# transformerboard.net
KiCad netlist of a schematic drawn in EAGLE
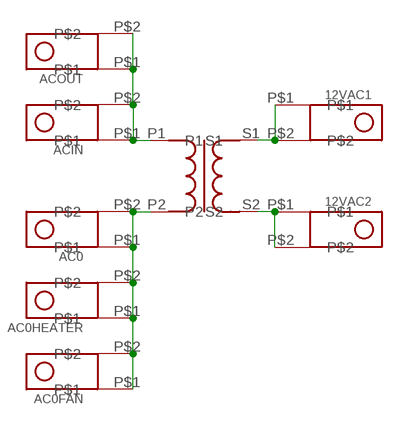
[diagram p0: schematic, sheet 1]

(export (version "E")
  (design (tool "Eeschema 10.0.6"))
  (components
    (comp (ref "12VAC1")
      (value "QUICKCONNECT-TAB")
      (footprint "eagle-import:QUICKCONNECT-TAB-6.35X0.81")
      (libsource (lib "eagle-import") (part "QUICKCONNECT-TAB"))
    )
    (comp (ref "12VAC2")
      (value "QUICKCONNECT-TAB")
      (footprint "eagle-import:QUICKCONNECT-TAB-6.35X0.81")
      (libsource (lib "eagle-import") (part "QUICKCONNECT-TAB"))
    )
    (comp (ref "AC0")
      (value "QUICKCONNECT-TAB")
      (footprint "eagle-import:QUICKCONNECT-TAB-6.35X0.81")
      (libsource (lib "eagle-import") (part "QUICKCONNECT-TAB"))
    )
    (comp (ref "AC0FAN")
      (value "QUICKCONNECT-TAB")
      (footprint "eagle-import:QUICKCONNECT-TAB-6.35X0.81")
      (libsource (lib "eagle-import") (part "QUICKCONNECT-TAB"))
    )
    (comp (ref "AC0HEATER")
      (value "QUICKCONNECT-TAB")
      (footprint "eagle-import:QUICKCONNECT-TAB-6.35X0.81")
      (libsource (lib "eagle-import") (part "QUICKCONNECT-TAB"))
    )
    (comp (ref "ACIN")
      (value "QUICKCONNECT-TAB")
      (footprint "eagle-import:QUICKCONNECT-TAB-6.35X0.81")
      (libsource (lib "eagle-import") (part "QUICKCONNECT-TAB"))
    )
    (comp (ref "ACOUT")
      (value "QUICKCONNECT-TAB")
      (footprint "eagle-import:QUICKCONNECT-TAB-6.35X0.81")
      (libsource (lib "eagle-import") (part "QUICKCONNECT-TAB"))
    )
    (comp (ref "T1")
      (value "TRANSFORMER")
      (footprint "eagle-import:1.6X1.4.X1.3")
      (libsource (lib "eagle-import") (part "TRANSFORMER"))
    )
  )
  (nets
    (net (code "1") (name "Net-(12VAC1-PadP$1)") (class "Default")
      (node (ref "12VAC1") (pin "P$1") (pinfunction "P$1_P$1") (pintype "bidirectional"))
      (node (ref "12VAC1") (pin "P$2") (pinfunction "P$2_P$2") (pintype "bidirectional"))
      (node (ref "T1") (pin "S1") (pinfunction "S1_S1") (pintype "bidirectional"))
    )
    (net (code "2") (name "Net-(12VAC2-PadP$1)") (class "Default")
      (node (ref "12VAC2") (pin "P$1") (pinfunction "P$1_P$1") (pintype "bidirectional"))
      (node (ref "12VAC2") (pin "P$2") (pinfunction "P$2_P$2") (pintype "bidirectional"))
      (node (ref "T1") (pin "S2") (pinfunction "S2_S2") (pintype "bidirectional"))
    )
    (net (code "3") (name "Net-(AC0-PadP$1)") (class "Default")
      (node (ref "AC0") (pin "P$1") (pinfunction "P$1_P$1") (pintype "bidirectional"))
      (node (ref "AC0") (pin "P$2") (pinfunction "P$2_P$2") (pintype "bidirectional"))
      (node (ref "AC0FAN") (pin "P$1") (pinfunction "P$1_P$1") (pintype "bidirectional"))
      (node (ref "AC0FAN") (pin "P$2") (pinfunction "P$2_P$2") (pintype "bidirectional"))
      (node (ref "AC0HEATER") (pin "P$1") (pinfunction "P$1_P$1") (pintype "bidirectional"))
      (node (ref "AC0HEATER") (pin "P$2") (pinfunction "P$2_P$2") (pintype "bidirectional"))
      (node (ref "T1") (pin "P2") (pinfunction "P2_P2") (pintype "bidirectional"))
    )
    (net (code "4") (name "Net-(ACIN-PadP$1)") (class "Default")
      (node (ref "ACIN") (pin "P$1") (pinfunction "P$1_P$1") (pintype "bidirectional"))
      (node (ref "ACIN") (pin "P$2") (pinfunction "P$2_P$2") (pintype "bidirectional"))
      (node (ref "ACOUT") (pin "P$1") (pinfunction "P$1_P$1") (pintype "bidirectional"))
      (node (ref "ACOUT") (pin "P$2") (pinfunction "P$2_P$2") (pintype "bidirectional"))
      (node (ref "T1") (pin "P1") (pinfunction "P1_P1") (pintype "bidirectional"))
    )
  )
)
